# fhd-hdr.net
KiCad netlist of a schematic drawn in Altium Designer
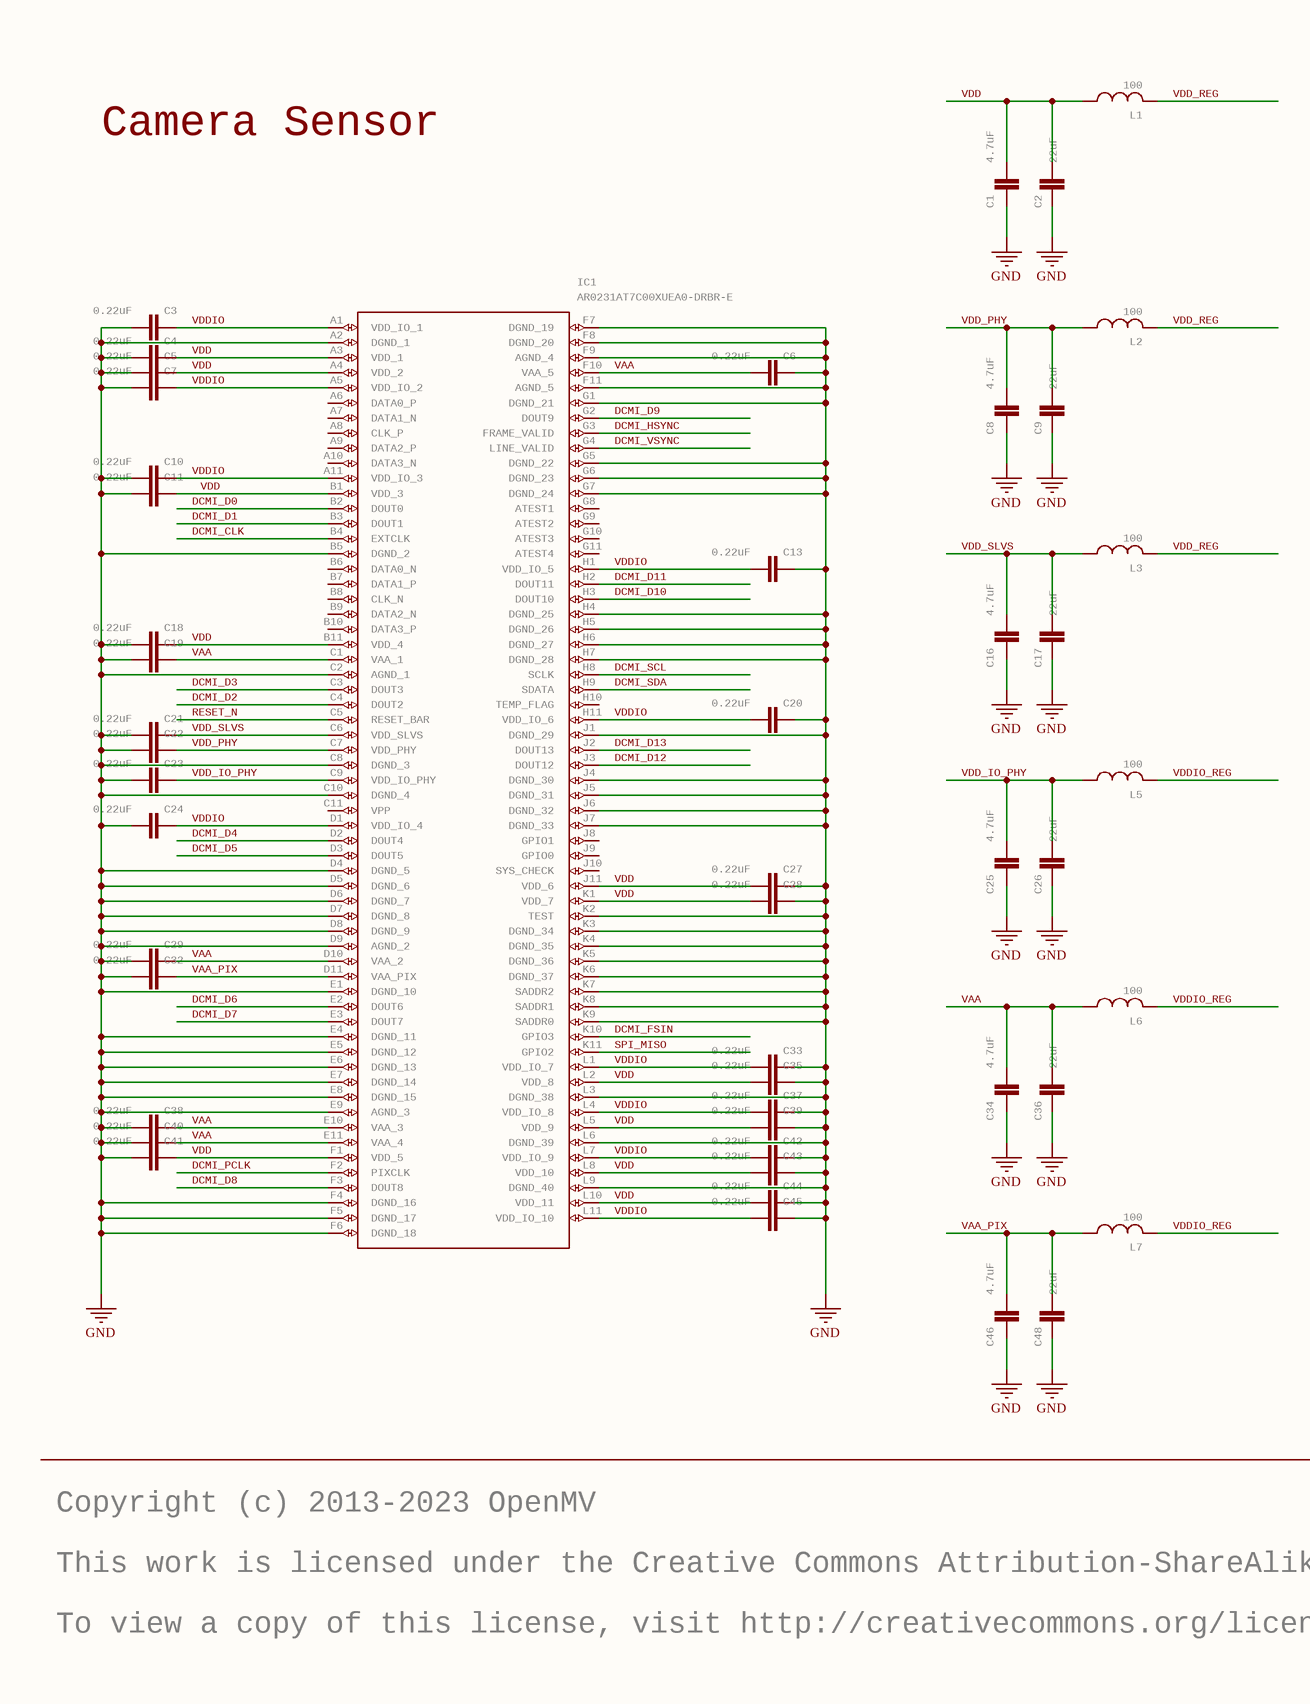
[diagram p0: fhd-hdr.SchDoc, left]
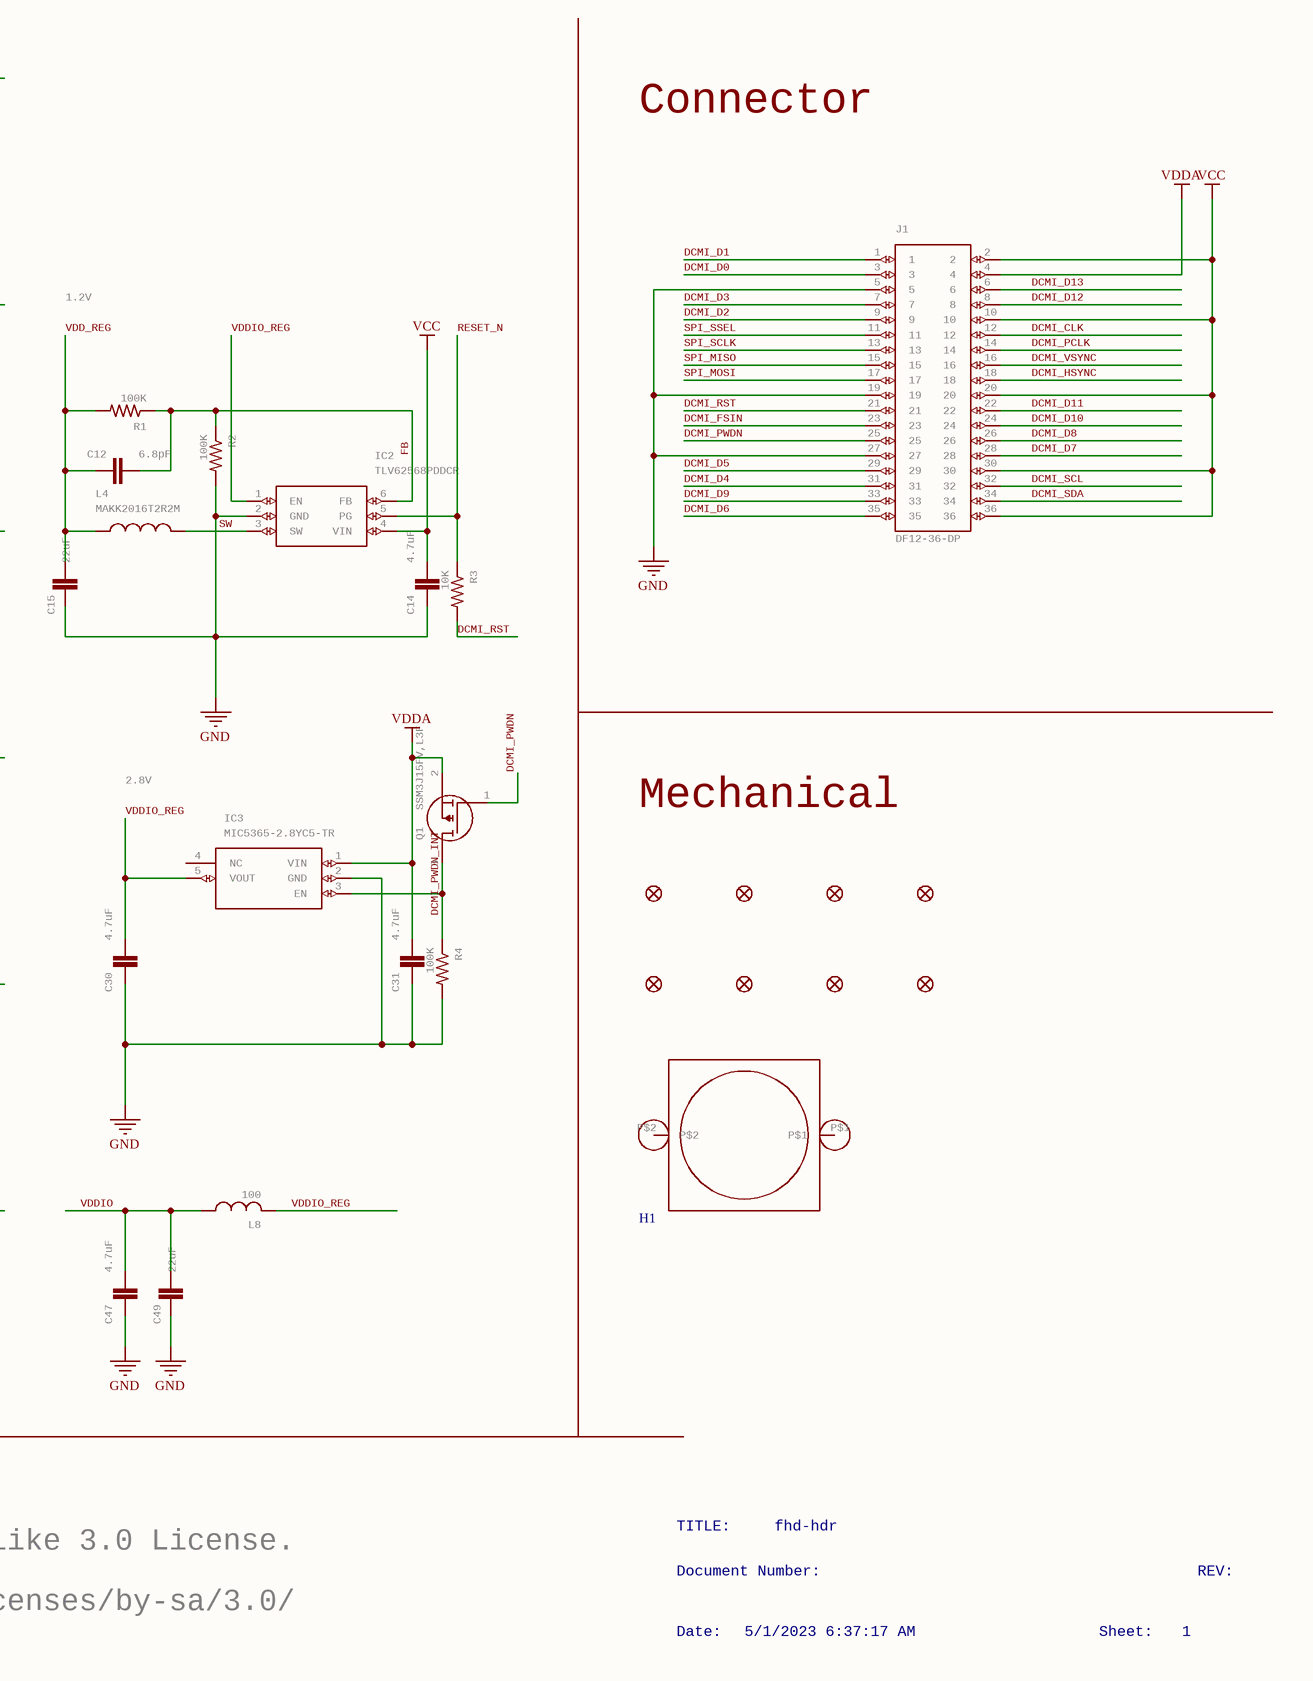
[diagram p1: fhd-hdr.SchDoc, right]

(export (version "E")
  (design (tool "Eeschema 10.0.6"))
  (components
    (comp (ref "C1")
      (value "4.7uF")
      (footprint "0402")
      (description "0402 (1005 Metric) Nick Garner - TeleSense")
      (fields (field (name "MPN") "JMK105BBJ475MV-F"))
      (libsource (lib "camera-modules") (part "CAP_0402"))
    )
    (comp (ref "C2")
      (value "22uF")
      (footprint "0805")
      (fields (field (name "MPN") "CL21A226MQQNNNE"))
      (libsource (lib "camera-modules") (part "22UF-0805-6.3V-20%"))
    )
    (comp (ref "C3")
      (value "0.22uF")
      (footprint "C0201")
      (description "CAPACITOR, European symbol")
      (fields (field (name "MPN") "GRM033R60J224ME15D"))
      (libsource (lib "camera-modules") (part "C-EUC0201"))
    )
    (comp (ref "C4")
      (value "0.22uF")
      (footprint "C0201")
      (description "CAPACITOR, European symbol")
      (fields (field (name "MPN") "GRM033R60J224ME15D"))
      (libsource (lib "camera-modules") (part "C-EUC0201"))
    )
    (comp (ref "C5")
      (value "0.22uF")
      (footprint "C0201")
      (description "CAPACITOR, European symbol")
      (fields (field (name "MPN") "GRM033R60J224ME15D"))
      (libsource (lib "camera-modules") (part "C-EUC0201"))
    )
    (comp (ref "C6")
      (value "0.22uF")
      (footprint "C0201")
      (description "CAPACITOR, European symbol")
      (fields (field (name "MPN") "GRM033R60J224ME15D"))
      (libsource (lib "camera-modules") (part "C-EUC0201"))
    )
    (comp (ref "C7")
      (value "0.22uF")
      (footprint "C0201")
      (description "CAPACITOR, European symbol")
      (fields (field (name "MPN") "GRM033R60J224ME15D"))
      (libsource (lib "camera-modules") (part "C-EUC0201"))
    )
    (comp (ref "C8")
      (value "4.7uF")
      (footprint "0402")
      (description "0402 (1005 Metric) Nick Garner - TeleSense")
      (fields (field (name "MPN") "JMK105BBJ475MV-F"))
      (libsource (lib "camera-modules") (part "CAP_0402"))
    )
    (comp (ref "C9")
      (value "22uF")
      (footprint "0805")
      (fields (field (name "MPN") "CL21A226MQQNNNE"))
      (libsource (lib "camera-modules") (part "22UF-0805-6.3V-20%"))
    )
    (comp (ref "C10")
      (value "0.22uF")
      (footprint "C0201")
      (description "CAPACITOR, European symbol")
      (fields (field (name "MPN") "GRM033R60J224ME15D"))
      (libsource (lib "camera-modules") (part "C-EUC0201"))
    )
    (comp (ref "C11")
      (value "0.22uF")
      (footprint "C0201")
      (description "CAPACITOR, European symbol")
      (fields (field (name "MPN") "GRM033R60J224ME15D"))
      (libsource (lib "camera-modules") (part "C-EUC0201"))
    )
    (comp (ref "C12")
      (value "6.8pF")
      (footprint "0402")
      (description "0402 (1005 Metric) Nick Garner - TeleSense")
      (fields (field (name "MPN") "GRM1555C1H6R8DA01D"))
      (libsource (lib "") (part "CAP_0402_1"))
    )
    (comp (ref "C13")
      (value "0.22uF")
      (footprint "C0201")
      (description "CAPACITOR, European symbol")
      (fields (field (name "MPN") "GRM033R60J224ME15D"))
      (libsource (lib "camera-modules") (part "C-EUC0201"))
    )
    (comp (ref "C14")
      (value "4.7uF")
      (footprint "0402")
      (description "0402 (1005 Metric) Nick Garner - TeleSense")
      (fields (field (name "MPN") "JMK105BBJ475MV-F"))
      (libsource (lib "camera-modules") (part "CAP_0402"))
    )
    (comp (ref "C15")
      (value "22uF")
      (footprint "0805")
      (fields (field (name "MPN") "CL21A226MQQNNNE"))
      (libsource (lib "camera-modules") (part "22UF-0805-6.3V-20%"))
    )
    (comp (ref "C16")
      (value "4.7uF")
      (footprint "0402")
      (description "0402 (1005 Metric) Nick Garner - TeleSense")
      (fields (field (name "MPN") "JMK105BBJ475MV-F"))
      (libsource (lib "camera-modules") (part "CAP_0402"))
    )
    (comp (ref "C17")
      (value "22uF")
      (footprint "0805")
      (fields (field (name "MPN") "CL21A226MQQNNNE"))
      (libsource (lib "camera-modules") (part "22UF-0805-6.3V-20%"))
    )
    (comp (ref "C18")
      (value "0.22uF")
      (footprint "C0201")
      (description "CAPACITOR, European symbol")
      (fields (field (name "MPN") "GRM033R60J224ME15D"))
      (libsource (lib "camera-modules") (part "C-EUC0201"))
    )
    (comp (ref "C19")
      (value "0.22uF")
      (footprint "C0201")
      (description "CAPACITOR, European symbol")
      (fields (field (name "MPN") "GRM033R60J224ME15D"))
      (libsource (lib "camera-modules") (part "C-EUC0201"))
    )
    (comp (ref "C20")
      (value "0.22uF")
      (footprint "C0201")
      (description "CAPACITOR, European symbol")
      (fields (field (name "MPN") "GRM033R60J224ME15D"))
      (libsource (lib "camera-modules") (part "C-EUC0201"))
    )
    (comp (ref "C21")
      (value "0.22uF")
      (footprint "C0201")
      (description "CAPACITOR, European symbol")
      (fields (field (name "MPN") "GRM033R60J224ME15D"))
      (libsource (lib "camera-modules") (part "C-EUC0201"))
    )
    (comp (ref "C22")
      (value "0.22uF")
      (footprint "C0201")
      (description "CAPACITOR, European symbol")
      (fields (field (name "MPN") "GRM033R60J224ME15D"))
      (libsource (lib "camera-modules") (part "C-EUC0201"))
    )
    (comp (ref "C23")
      (value "0.22uF")
      (footprint "C0201")
      (description "CAPACITOR, European symbol")
      (fields (field (name "MPN") "GRM033R60J224ME15D"))
      (libsource (lib "camera-modules") (part "C-EUC0201"))
    )
    (comp (ref "C24")
      (value "0.22uF")
      (footprint "C0201")
      (description "CAPACITOR, European symbol")
      (fields (field (name "MPN") "GRM033R60J224ME15D"))
      (libsource (lib "camera-modules") (part "C-EUC0201"))
    )
    (comp (ref "C25")
      (value "4.7uF")
      (footprint "0402")
      (description "0402 (1005 Metric) Nick Garner - TeleSense")
      (fields (field (name "MPN") "JMK105BBJ475MV-F"))
      (libsource (lib "camera-modules") (part "CAP_0402"))
    )
    (comp (ref "C26")
      (value "22uF")
      (footprint "0805")
      (fields (field (name "MPN") "CL21A226MQQNNNE"))
      (libsource (lib "camera-modules") (part "22UF-0805-6.3V-20%"))
    )
    (comp (ref "C27")
      (value "0.22uF")
      (footprint "C0201")
      (description "CAPACITOR, European symbol")
      (fields (field (name "MPN") "GRM033R60J224ME15D"))
      (libsource (lib "camera-modules") (part "C-EUC0201"))
    )
    (comp (ref "C28")
      (value "0.22uF")
      (footprint "C0201")
      (description "CAPACITOR, European symbol")
      (fields (field (name "MPN") "GRM033R60J224ME15D"))
      (libsource (lib "camera-modules") (part "C-EUC0201"))
    )
    (comp (ref "C29")
      (value "0.22uF")
      (footprint "C0201")
      (description "CAPACITOR, European symbol")
      (fields (field (name "MPN") "GRM033R60J224ME15D"))
      (libsource (lib "camera-modules") (part "C-EUC0201"))
    )
    (comp (ref "C30")
      (value "4.7uF")
      (footprint "0402")
      (description "0402 (1005 Metric) Nick Garner - TeleSense")
      (fields (field (name "MPN") "JMK105BBJ475MV-F"))
      (libsource (lib "camera-modules") (part "CAP_0402"))
    )
    (comp (ref "C31")
      (value "4.7uF")
      (footprint "0402")
      (description "0402 (1005 Metric) Nick Garner - TeleSense")
      (fields (field (name "MPN") "JMK105BBJ475MV-F"))
      (libsource (lib "camera-modules") (part "CAP_0402"))
    )
    (comp (ref "C32")
      (value "0.22uF")
      (footprint "C0201")
      (description "CAPACITOR, European symbol")
      (fields (field (name "MPN") "GRM033R60J224ME15D"))
      (libsource (lib "camera-modules") (part "C-EUC0201"))
    )
    (comp (ref "C33")
      (value "0.22uF")
      (footprint "C0201")
      (description "CAPACITOR, European symbol")
      (fields (field (name "MPN") "GRM033R60J224ME15D"))
      (libsource (lib "camera-modules") (part "C-EUC0201"))
    )
    (comp (ref "C34")
      (value "4.7uF")
      (footprint "0402")
      (description "0402 (1005 Metric) Nick Garner - TeleSense")
      (fields (field (name "MPN") "JMK105BBJ475MV-F"))
      (libsource (lib "camera-modules") (part "CAP_0402"))
    )
    (comp (ref "C35")
      (value "0.22uF")
      (footprint "C0201")
      (description "CAPACITOR, European symbol")
      (fields (field (name "MPN") "GRM033R60J224ME15D"))
      (libsource (lib "camera-modules") (part "C-EUC0201"))
    )
    (comp (ref "C36")
      (value "22uF")
      (footprint "0805")
      (fields (field (name "MPN") "CL21A226MQQNNNE"))
      (libsource (lib "camera-modules") (part "22UF-0805-6.3V-20%"))
    )
    (comp (ref "C37")
      (value "0.22uF")
      (footprint "C0201")
      (description "CAPACITOR, European symbol")
      (fields (field (name "MPN") "GRM033R60J224ME15D"))
      (libsource (lib "camera-modules") (part "C-EUC0201"))
    )
    (comp (ref "C38")
      (value "0.22uF")
      (footprint "C0201")
      (description "CAPACITOR, European symbol")
      (fields (field (name "MPN") "GRM033R60J224ME15D"))
      (libsource (lib "camera-modules") (part "C-EUC0201"))
    )
    (comp (ref "C39")
      (value "0.22uF")
      (footprint "C0201")
      (description "CAPACITOR, European symbol")
      (fields (field (name "MPN") "GRM033R60J224ME15D"))
      (libsource (lib "camera-modules") (part "C-EUC0201"))
    )
    (comp (ref "C40")
      (value "0.22uF")
      (footprint "C0201")
      (description "CAPACITOR, European symbol")
      (fields (field (name "MPN") "GRM033R60J224ME15D"))
      (libsource (lib "camera-modules") (part "C-EUC0201"))
    )
    (comp (ref "C41")
      (value "0.22uF")
      (footprint "C0201")
      (description "CAPACITOR, European symbol")
      (fields (field (name "MPN") "GRM033R60J224ME15D"))
      (libsource (lib "camera-modules") (part "C-EUC0201"))
    )
    (comp (ref "C42")
      (value "0.22uF")
      (footprint "C0201")
      (description "CAPACITOR, European symbol")
      (fields (field (name "MPN") "GRM033R60J224ME15D"))
      (libsource (lib "camera-modules") (part "C-EUC0201"))
    )
    (comp (ref "C43")
      (value "0.22uF")
      (footprint "C0201")
      (description "CAPACITOR, European symbol")
      (fields (field (name "MPN") "GRM033R60J224ME15D"))
      (libsource (lib "camera-modules") (part "C-EUC0201"))
    )
    (comp (ref "C44")
      (value "0.22uF")
      (footprint "C0201")
      (description "CAPACITOR, European symbol")
      (fields (field (name "MPN") "GRM033R60J224ME15D"))
      (libsource (lib "camera-modules") (part "C-EUC0201"))
    )
    (comp (ref "C45")
      (value "0.22uF")
      (footprint "C0201")
      (description "CAPACITOR, European symbol")
      (fields (field (name "MPN") "GRM033R60J224ME15D"))
      (libsource (lib "camera-modules") (part "C-EUC0201"))
    )
    (comp (ref "C46")
      (value "4.7uF")
      (footprint "0402")
      (description "0402 (1005 Metric) Nick Garner - TeleSense")
      (fields (field (name "MPN") "JMK105BBJ475MV-F"))
      (libsource (lib "camera-modules") (part "CAP_0402"))
    )
    (comp (ref "C47")
      (value "4.7uF")
      (footprint "0402")
      (description "0402 (1005 Metric) Nick Garner - TeleSense")
      (fields (field (name "MPN") "JMK105BBJ475MV-F"))
      (libsource (lib "camera-modules") (part "CAP_0402"))
    )
    (comp (ref "C48")
      (value "22uF")
      (footprint "0805")
      (fields (field (name "MPN") "CL21A226MQQNNNE"))
      (libsource (lib "camera-modules") (part "22UF-0805-6.3V-20%"))
    )
    (comp (ref "C49")
      (value "22uF")
      (footprint "0805")
      (fields (field (name "MPN") "CL21A226MQQNNNE"))
      (libsource (lib "camera-modules") (part "22UF-0805-6.3V-20%"))
    )
    (comp (ref "FD1")
      (value "FIDUCIAL1X2")
      (footprint "FIDUCIAL-1X2")
      (fields (field (name "LIBRARYNAME") "SparkFun-Aesthetics"))
      (libsource (lib "camera-modules") (part "FIDUCIAL1X2"))
    )
    (comp (ref "FD2")
      (value "FIDUCIAL1X2")
      (footprint "FIDUCIAL-1X2")
      (fields (field (name "LIBRARYNAME") "SparkFun-Aesthetics"))
      (libsource (lib "camera-modules") (part "FIDUCIAL1X2"))
    )
    (comp (ref "FD3")
      (value "FIDUCIAL1X2")
      (footprint "FIDUCIAL-1X2")
      (fields (field (name "LIBRARYNAME") "SparkFun-Aesthetics"))
      (libsource (lib "camera-modules") (part "FIDUCIAL1X2"))
    )
    (comp (ref "FD4")
      (value "FIDUCIAL1X2")
      (footprint "FIDUCIAL-1X2")
      (fields (field (name "LIBRARYNAME") "SparkFun-Aesthetics"))
      (libsource (lib "camera-modules") (part "FIDUCIAL1X2"))
    )
    (comp (ref "FD5")
      (value "FIDUCIAL1X2")
      (footprint "FIDUCIAL-1X2")
      (fields (field (name "LIBRARYNAME") "SparkFun-Aesthetics"))
      (libsource (lib "camera-modules") (part "FIDUCIAL1X2"))
    )
    (comp (ref "FD6")
      (value "FIDUCIAL1X2")
      (footprint "FIDUCIAL-1X2")
      (fields (field (name "LIBRARYNAME") "SparkFun-Aesthetics"))
      (libsource (lib "camera-modules") (part "FIDUCIAL1X2"))
    )
    (comp (ref "FD7")
      (value "FIDUCIAL1X2")
      (footprint "FIDUCIAL-1X2")
      (fields (field (name "LIBRARYNAME") "SparkFun-Aesthetics"))
      (libsource (lib "camera-modules") (part "FIDUCIAL1X2"))
    )
    (comp (ref "FD8")
      (value "FIDUCIAL1X2")
      (footprint "FIDUCIAL-1X2")
      (fields (field (name "LIBRARYNAME") "SparkFun-Aesthetics"))
      (libsource (lib "camera-modules") (part "FIDUCIAL1X2"))
    )
    (comp (ref "H1")
      (value "LENSMOUNT20MM")
      (footprint "LENSMOUNT-20MM")
      (libsource (lib "camera-modules") (part "LENSMOUNT20MM"))
    )
    (comp (ref "IC1")
      (value "AR0231AT7C00XUEA0-DRBR-E")
      (footprint "BGA121C80P11X11_1100X1000X155")
      (description "Image Sensor Color CMOS 1928 x 1208Pixels   Source:  Datasheet")
      (fields
        (field (name "ARROW_PART_NUMBER") "ARROW_PART_NUMBER")
        (field (name "MOUSER_PART_NUMBER") "MOUSER_PART_NUMBER")
      )
      (libsource (lib "camera-modules") (part "AR0231AT7C00XUEA0-DRBR-E"))
    )
    (comp (ref "IC2")
      (value "TLV62568PDDCR")
      (footprint "SOT95P280X110-6N")
      (fields (field (name "MOUSER_PART_NUMBER") "595-TLV62568PDDCR"))
      (libsource (lib "camera-modules") (part "TLV62568PDDCR"))
    )
    (comp (ref "IC3")
      (value "MIC5365-2.8YC5-TR")
      (footprint "SOT65P210X110-5N")
      (description "IC REG LINEAR 2.8V 150MA SC70-5   Source:  Datasheet")
      (fields (field (name "MOUSER_PART_NUMBER") "998-MIC5365-2.8YC5TR"))
      (libsource (lib "camera-modules") (part "MIC5365-2.8YC5-TR"))
    )
    (comp (ref "J1")
      (value "DF12-36-DP")
      (footprint "DF12-36-DP")
      (fields (field (name "MPN") "DF12NB(3.0)-36DP-0.5V(51)"))
      (libsource (lib "camera-modules") (part "DF12-36-DP"))
    )
    (comp (ref "L1")
      (value "100")
      (footprint "0402")
      (fields (field (name "MPN") "MFBM1V1005-101-R"))
      (libsource (lib "camera-modules") (part "INDUCTOR_0402"))
    )
    (comp (ref "L2")
      (value "100")
      (footprint "0402")
      (fields (field (name "MPN") "MFBM1V1005-101-R"))
      (libsource (lib "camera-modules") (part "INDUCTOR_0402"))
    )
    (comp (ref "L3")
      (value "100")
      (footprint "0402")
      (fields (field (name "MPN") "MFBM1V1005-101-R"))
      (libsource (lib "camera-modules") (part "INDUCTOR_0402"))
    )
    (comp (ref "L4")
      (value "MAKK2016T2R2M")
      (footprint "INDC2016X100N")
      (description "INDUCTOR, METAL CORE Check availability")
      (fields (field (name "MF") "Taiyo Yuden"))
      (libsource (lib "camera-modules") (part "MAKK2016T2R2M"))
    )
    (comp (ref "L5")
      (value "100")
      (footprint "0402")
      (fields (field (name "MPN") "MFBM1V1005-101-R"))
      (libsource (lib "camera-modules") (part "INDUCTOR_0402"))
    )
    (comp (ref "L6")
      (value "100")
      (footprint "0402")
      (fields (field (name "MPN") "MFBM1V1005-101-R"))
      (libsource (lib "camera-modules") (part "INDUCTOR_0402"))
    )
    (comp (ref "L7")
      (value "100")
      (footprint "0402")
      (fields (field (name "MPN") "MFBM1V1005-101-R"))
      (libsource (lib "camera-modules") (part "INDUCTOR_0402"))
    )
    (comp (ref "L8")
      (value "100")
      (footprint "0402")
      (fields (field (name "MPN") "MFBM1V1005-101-R"))
      (libsource (lib "camera-modules") (part "INDUCTOR_0402"))
    )
    (comp (ref "Q1")
      (value "SSM3J15FV,L3F")
      (footprint "SSM3J15FV")
      (description "MOSFET 30 V, P-channel Trench MOSFET   Source:  Datasheet")
      (libsource (lib "camera-modules") (part "PMXB120EPEZ"))
    )
    (comp (ref "R1")
      (value "100K")
      (footprint "R0402")
      (description "RESISTOR, American symbol")
      (fields (field (name "MPN") "AC0402FR-07100KL"))
      (libsource (lib "camera-modules") (part "R-US_R0402"))
    )
    (comp (ref "R2")
      (value "100K")
      (footprint "R0402")
      (description "RESISTOR, American symbol")
      (fields (field (name "MPN") "AC0402FR-07100KL"))
      (libsource (lib "camera-modules") (part "R-US_R0402"))
    )
    (comp (ref "R3")
      (value "10K")
      (footprint "R0402")
      (description "RESISTOR, American symbol")
      (fields (field (name "MPN") "AC0402FR-1310KL"))
      (libsource (lib "camera-modules") (part "R-US_R0402"))
    )
    (comp (ref "R4")
      (value "100K")
      (footprint "R0402")
      (description "RESISTOR, American symbol")
      (fields (field (name "MPN") "AC0402FR-07100KL"))
      (libsource (lib "camera-modules") (part "R-US_R0402"))
    )
  )
  (nets
    (net (code "1") (name "/DCMI_CLK") (class "Default")
      (node (ref "IC1") (pin "B4") (pinfunction "EXTCLK_B4") (pintype "bidirectional"))
      (node (ref "J1") (pin "12") (pinfunction "12_12") (pintype "bidirectional"))
    )
    (net (code "2") (name "/DCMI_D0") (class "Default")
      (node (ref "IC1") (pin "B2") (pinfunction "DOUT0_B2") (pintype "bidirectional"))
      (node (ref "J1") (pin "3") (pinfunction "3_3") (pintype "bidirectional"))
    )
    (net (code "3") (name "/DCMI_D1") (class "Default")
      (node (ref "IC1") (pin "B3") (pinfunction "DOUT1_B3") (pintype "bidirectional"))
      (node (ref "J1") (pin "1") (pinfunction "1_1") (pintype "bidirectional"))
    )
    (net (code "4") (name "/DCMI_D2") (class "Default")
      (node (ref "IC1") (pin "C4") (pinfunction "DOUT2_C4") (pintype "bidirectional"))
      (node (ref "J1") (pin "9") (pinfunction "9_9") (pintype "bidirectional"))
    )
    (net (code "5") (name "/DCMI_D3") (class "Default")
      (node (ref "IC1") (pin "C3") (pinfunction "DOUT3_C3") (pintype "bidirectional"))
      (node (ref "J1") (pin "7") (pinfunction "7_7") (pintype "bidirectional"))
    )
    (net (code "6") (name "/DCMI_D4") (class "Default")
      (node (ref "IC1") (pin "D2") (pinfunction "DOUT4_D2") (pintype "bidirectional"))
      (node (ref "J1") (pin "31") (pinfunction "31_31") (pintype "bidirectional"))
    )
    (net (code "7") (name "/DCMI_D5") (class "Default")
      (node (ref "IC1") (pin "D3") (pinfunction "DOUT5_D3") (pintype "bidirectional"))
      (node (ref "J1") (pin "29") (pinfunction "29_29") (pintype "bidirectional"))
    )
    (net (code "8") (name "/DCMI_D6") (class "Default")
      (node (ref "IC1") (pin "E2") (pinfunction "DOUT6_E2") (pintype "bidirectional"))
      (node (ref "J1") (pin "35") (pinfunction "35_35") (pintype "bidirectional"))
    )
    (net (code "9") (name "/DCMI_D7") (class "Default")
      (node (ref "IC1") (pin "E3") (pinfunction "DOUT7_E3") (pintype "bidirectional"))
      (node (ref "J1") (pin "28") (pinfunction "28_28") (pintype "bidirectional"))
    )
    (net (code "10") (name "/DCMI_D8") (class "Default")
      (node (ref "IC1") (pin "F3") (pinfunction "DOUT8_F3") (pintype "bidirectional"))
      (node (ref "J1") (pin "26") (pinfunction "26_26") (pintype "bidirectional"))
    )
    (net (code "11") (name "/DCMI_D9") (class "Default")
      (node (ref "IC1") (pin "G2") (pinfunction "DOUT9_G2") (pintype "bidirectional"))
      (node (ref "J1") (pin "33") (pinfunction "33_33") (pintype "bidirectional"))
    )
    (net (code "12") (name "/DCMI_D10") (class "Default")
      (node (ref "IC1") (pin "H3") (pinfunction "DOUT10_H3") (pintype "bidirectional"))
      (node (ref "J1") (pin "24") (pinfunction "24_24") (pintype "bidirectional"))
    )
    (net (code "13") (name "/DCMI_D11") (class "Default")
      (node (ref "IC1") (pin "H2") (pinfunction "DOUT11_H2") (pintype "bidirectional"))
      (node (ref "J1") (pin "22") (pinfunction "22_22") (pintype "bidirectional"))
    )
    (net (code "14") (name "/DCMI_D12") (class "Default")
      (node (ref "IC1") (pin "J3") (pinfunction "DOUT12_J3") (pintype "bidirectional"))
      (node (ref "J1") (pin "8") (pinfunction "8_8") (pintype "bidirectional"))
    )
    (net (code "15") (name "/DCMI_D13") (class "Default")
      (node (ref "IC1") (pin "J2") (pinfunction "DOUT13_J2") (pintype "bidirectional"))
      (node (ref "J1") (pin "6") (pinfunction "6_6") (pintype "bidirectional"))
    )
    (net (code "16") (name "/DCMI_FSIN") (class "Default")
      (node (ref "IC1") (pin "K10") (pinfunction "GPIO3_K10") (pintype "bidirectional"))
      (node (ref "J1") (pin "23") (pinfunction "23_23") (pintype "bidirectional"))
    )
    (net (code "17") (name "/DCMI_HSYNC") (class "Default")
      (node (ref "IC1") (pin "G3") (pinfunction "FRAME_VALID_G3") (pintype "bidirectional"))
      (node (ref "J1") (pin "18") (pinfunction "18_18") (pintype "bidirectional"))
    )
    (net (code "18") (name "/DCMI_PCLK") (class "Default")
      (node (ref "IC1") (pin "F2") (pinfunction "PIXCLK_F2") (pintype "bidirectional"))
      (node (ref "J1") (pin "14") (pinfunction "14_14") (pintype "bidirectional"))
    )
    (net (code "19") (name "/DCMI_PWDN") (class "Default")
      (node (ref "J1") (pin "25") (pinfunction "25_25") (pintype "bidirectional"))
      (node (ref "Q1") (pin "1") (pinfunction "G_1") (pintype "bidirectional"))
    )
    (net (code "20") (name "/DCMI_PWDN_INT") (class "Default")
      (node (ref "IC3") (pin "3") (pinfunction "EN_3") (pintype "bidirectional"))
      (node (ref "Q1") (pin "3") (pinfunction "D_3") (pintype "bidirectional"))
      (node (ref "R4") (pin "1") (pinfunction "1_1") (pintype "passive"))
    )
    (net (code "21") (name "/DCMI_RST") (class "Default")
      (node (ref "J1") (pin "21") (pinfunction "21_21") (pintype "bidirectional"))
      (node (ref "R3") (pin "2") (pinfunction "2_2") (pintype "passive"))
    )
    (net (code "22") (name "/DCMI_SCL") (class "Default")
      (node (ref "IC1") (pin "H8") (pinfunction "SCLK_H8") (pintype "bidirectional"))
      (node (ref "J1") (pin "32") (pinfunction "32_32") (pintype "bidirectional"))
    )
    (net (code "23") (name "/DCMI_SDA") (class "Default")
      (node (ref "IC1") (pin "H9") (pinfunction "SDATA_H9") (pintype "bidirectional"))
      (node (ref "J1") (pin "34") (pinfunction "34_34") (pintype "bidirectional"))
    )
    (net (code "24") (name "/DCMI_VSYNC") (class "Default")
      (node (ref "IC1") (pin "G4") (pinfunction "LINE_VALID_G4") (pintype "bidirectional"))
      (node (ref "J1") (pin "16") (pinfunction "16_16") (pintype "bidirectional"))
    )
    (net (code "25") (name "/FB") (class "Default")
      (node (ref "C12") (pin "2") (pinfunction "2_2") (pintype "passive"))
      (node (ref "IC2") (pin "6") (pinfunction "FB_6") (pintype "bidirectional"))
      (node (ref "R1") (pin "1") (pinfunction "1_1") (pintype "passive"))
      (node (ref "R2") (pin "1") (pinfunction "1_1") (pintype "passive"))
    )
    (net (code "26") (name "/RESET_N") (class "Default")
      (node (ref "IC1") (pin "C5") (pinfunction "RESET_BAR_C5") (pintype "bidirectional"))
      (node (ref "IC2") (pin "5") (pinfunction "PG_5") (pintype "bidirectional"))
      (node (ref "R3") (pin "1") (pinfunction "1_1") (pintype "passive"))
    )
    (net (code "27") (name "/SPI_MISO") (class "Default")
      (node (ref "IC1") (pin "K11") (pinfunction "GPIO2_K11") (pintype "bidirectional"))
      (node (ref "J1") (pin "15") (pinfunction "15_15") (pintype "bidirectional"))
    )
    (net (code "28") (name "/SPI_MOSI") (class "Default")
      (node (ref "J1") (pin "17") (pinfunction "17_17") (pintype "bidirectional"))
    )
    (net (code "29") (name "/SPI_SCLK") (class "Default")
      (node (ref "J1") (pin "13") (pinfunction "13_13") (pintype "bidirectional"))
    )
    (net (code "30") (name "/SPI_SSEL") (class "Default")
      (node (ref "J1") (pin "11") (pinfunction "11_11") (pintype "bidirectional"))
    )
    (net (code "31") (name "/SW") (class "Default")
      (node (ref "IC2") (pin "3") (pinfunction "SW_3") (pintype "bidirectional"))
      (node (ref "L4") (pin "2") (pinfunction "2_2") (pintype "passive"))
    )
    (net (code "32") (name "/VAA") (class "Default")
      (node (ref "C19") (pin "1") (pinfunction "1_1") (pintype "passive"))
      (node (ref "C29") (pin "1") (pinfunction "1_1") (pintype "passive"))
      (node (ref "C34") (pin "2") (pinfunction "2_2") (pintype "passive"))
      (node (ref "C36") (pin "2") (pinfunction "2_2") (pintype "passive"))
      (node (ref "C38") (pin "1") (pinfunction "1_1") (pintype "passive"))
      (node (ref "C40") (pin "1") (pinfunction "1_1") (pintype "passive"))
      (node (ref "C6") (pin "2") (pinfunction "2_2") (pintype "passive"))
      (node (ref "IC1") (pin "C1") (pinfunction "VAA_1_C1") (pintype "bidirectional"))
      (node (ref "IC1") (pin "D10") (pinfunction "VAA_2_D10") (pintype "bidirectional"))
      (node (ref "IC1") (pin "E10") (pinfunction "VAA_3_E10") (pintype "bidirectional"))
      (node (ref "IC1") (pin "E11") (pinfunction "VAA_4_E11") (pintype "bidirectional"))
      (node (ref "IC1") (pin "F10") (pinfunction "VAA_5_F10") (pintype "bidirectional"))
      (node (ref "L6") (pin "1") (pinfunction "P$1_1") (pintype "passive"))
    )
    (net (code "33") (name "/VAA_PIX") (class "Default")
      (node (ref "C32") (pin "1") (pinfunction "1_1") (pintype "passive"))
      (node (ref "C46") (pin "2") (pinfunction "2_2") (pintype "passive"))
      (node (ref "C48") (pin "2") (pinfunction "2_2") (pintype "passive"))
      (node (ref "IC1") (pin "D11") (pinfunction "VAA_PIX_D11") (pintype "bidirectional"))
      (node (ref "L7") (pin "1") (pinfunction "P$1_1") (pintype "passive"))
    )
    (net (code "34") (name "/VDD") (class "Default")
      (node (ref "C1") (pin "2") (pinfunction "2_2") (pintype "passive"))
      (node (ref "C11") (pin "1") (pinfunction "1_1") (pintype "passive"))
      (node (ref "C18") (pin "1") (pinfunction "1_1") (pintype "passive"))
      (node (ref "C2") (pin "2") (pinfunction "2_2") (pintype "passive"))
      (node (ref "C27") (pin "2") (pinfunction "2_2") (pintype "passive"))
      (node (ref "C28") (pin "2") (pinfunction "2_2") (pintype "passive"))
      (node (ref "C35") (pin "2") (pinfunction "2_2") (pintype "passive"))
      (node (ref "C39") (pin "2") (pinfunction "2_2") (pintype "passive"))
      (node (ref "C4") (pin "1") (pinfunction "1_1") (pintype "passive"))
      (node (ref "C41") (pin "1") (pinfunction "1_1") (pintype "passive"))
      (node (ref "C43") (pin "2") (pinfunction "2_2") (pintype "passive"))
      (node (ref "C44") (pin "2") (pinfunction "2_2") (pintype "passive"))
      (node (ref "C5") (pin "1") (pinfunction "1_1") (pintype "passive"))
      (node (ref "IC1") (pin "A3") (pinfunction "VDD_1_A3") (pintype "bidirectional"))
      (node (ref "IC1") (pin "A4") (pinfunction "VDD_2_A4") (pintype "bidirectional"))
      (node (ref "IC1") (pin "B1") (pinfunction "VDD_3_B1") (pintype "bidirectional"))
      (node (ref "IC1") (pin "B11") (pinfunction "VDD_4_B11") (pintype "bidirectional"))
      (node (ref "IC1") (pin "F1") (pinfunction "VDD_5_F1") (pintype "bidirectional"))
      (node (ref "IC1") (pin "J11") (pinfunction "VDD_6_J11") (pintype "bidirectional"))
      (node (ref "IC1") (pin "K1") (pinfunction "VDD_7_K1") (pintype "bidirectional"))
      (node (ref "IC1") (pin "L10") (pinfunction "VDD_11_L10") (pintype "bidirectional"))
      (node (ref "IC1") (pin "L2") (pinfunction "VDD_8_L2") (pintype "bidirectional"))
      (node (ref "IC1") (pin "L5") (pinfunction "VDD_9_L5") (pintype "bidirectional"))
      (node (ref "IC1") (pin "L8") (pinfunction "VDD_10_L8") (pintype "bidirectional"))
      (node (ref "L1") (pin "1") (pinfunction "P$1_1") (pintype "passive"))
    )
    (net (code "35") (name "/VDDIO") (class "Default")
      (node (ref "C10") (pin "1") (pinfunction "1_1") (pintype "passive"))
      (node (ref "C13") (pin "2") (pinfunction "2_2") (pintype "passive"))
      (node (ref "C20") (pin "2") (pinfunction "2_2") (pintype "passive"))
      (node (ref "C24") (pin "1") (pinfunction "1_1") (pintype "passive"))
      (node (ref "C3") (pin "1") (pinfunction "1_1") (pintype "passive"))
      (node (ref "C33") (pin "2") (pinfunction "2_2") (pintype "passive"))
      (node (ref "C37") (pin "2") (pinfunction "2_2") (pintype "passive"))
      (node (ref "C42") (pin "2") (pinfunction "2_2") (pintype "passive"))
      (node (ref "C45") (pin "2") (pinfunction "2_2") (pintype "passive"))
      (node (ref "C47") (pin "2") (pinfunction "2_2") (pintype "passive"))
      (node (ref "C49") (pin "2") (pinfunction "2_2") (pintype "passive"))
      (node (ref "C7") (pin "1") (pinfunction "1_1") (pintype "passive"))
      (node (ref "IC1") (pin "A1") (pinfunction "VDD_IO_1_A1") (pintype "bidirectional"))
      (node (ref "IC1") (pin "A11") (pinfunction "VDD_IO_3_A11") (pintype "bidirectional"))
      (node (ref "IC1") (pin "A5") (pinfunction "VDD_IO_2_A5") (pintype "bidirectional"))
      (node (ref "IC1") (pin "D1") (pinfunction "VDD_IO_4_D1") (pintype "bidirectional"))
      (node (ref "IC1") (pin "H1") (pinfunction "VDD_IO_5_H1") (pintype "bidirectional"))
      (node (ref "IC1") (pin "H11") (pinfunction "VDD_IO_6_H11") (pintype "bidirectional"))
      (node (ref "IC1") (pin "L1") (pinfunction "VDD_IO_7_L1") (pintype "bidirectional"))
      (node (ref "IC1") (pin "L11") (pinfunction "VDD_IO_10_L11") (pintype "bidirectional"))
      (node (ref "IC1") (pin "L4") (pinfunction "VDD_IO_8_L4") (pintype "bidirectional"))
      (node (ref "IC1") (pin "L7") (pinfunction "VDD_IO_9_L7") (pintype "bidirectional"))
      (node (ref "L8") (pin "1") (pinfunction "P$1_1") (pintype "passive"))
    )
    (net (code "36") (name "/VDDIO_REG") (class "Default")
      (node (ref "C30") (pin "2") (pinfunction "2_2") (pintype "passive"))
      (node (ref "IC2") (pin "1") (pinfunction "EN_1") (pintype "bidirectional"))
      (node (ref "IC3") (pin "5") (pinfunction "VOUT_5") (pintype "bidirectional"))
      (node (ref "L5") (pin "2") (pinfunction "P$2_2") (pintype "passive"))
      (node (ref "L6") (pin "2") (pinfunction "P$2_2") (pintype "passive"))
      (node (ref "L7") (pin "2") (pinfunction "P$2_2") (pintype "passive"))
      (node (ref "L8") (pin "2") (pinfunction "P$2_2") (pintype "passive"))
    )
    (net (code "37") (name "/VDD_IO_PHY") (class "Default")
      (node (ref "C23") (pin "1") (pinfunction "1_1") (pintype "passive"))
      (node (ref "C25") (pin "2") (pinfunction "2_2") (pintype "passive"))
      (node (ref "C26") (pin "2") (pinfunction "2_2") (pintype "passive"))
      (node (ref "IC1") (pin "C9") (pinfunction "VDD_IO_PHY_C9") (pintype "bidirectional"))
      (node (ref "L5") (pin "1") (pinfunction "P$1_1") (pintype "passive"))
    )
    (net (code "38") (name "/VDD_PHY") (class "Default")
      (node (ref "C22") (pin "1") (pinfunction "1_1") (pintype "passive"))
      (node (ref "C8") (pin "2") (pinfunction "2_2") (pintype "passive"))
      (node (ref "C9") (pin "2") (pinfunction "2_2") (pintype "passive"))
      (node (ref "IC1") (pin "C7") (pinfunction "VDD_PHY_C7") (pintype "bidirectional"))
      (node (ref "L2") (pin "1") (pinfunction "P$1_1") (pintype "passive"))
    )
    (net (code "39") (name "/VDD_REG") (class "Default")
      (node (ref "C12") (pin "1") (pinfunction "1_1") (pintype "passive"))
      (node (ref "C15") (pin "2") (pinfunction "2_2") (pintype "passive"))
      (node (ref "L1") (pin "2") (pinfunction "P$2_2") (pintype "passive"))
      (node (ref "L2") (pin "2") (pinfunction "P$2_2") (pintype "passive"))
      (node (ref "L3") (pin "2") (pinfunction "P$2_2") (pintype "passive"))
      (node (ref "L4") (pin "1") (pinfunction "1_1") (pintype "passive"))
      (node (ref "R1") (pin "2") (pinfunction "2_2") (pintype "passive"))
    )
    (net (code "40") (name "/VDD_SLVS") (class "Default")
      (node (ref "C16") (pin "2") (pinfunction "2_2") (pintype "passive"))
      (node (ref "C17") (pin "2") (pinfunction "2_2") (pintype "passive"))
      (node (ref "C21") (pin "1") (pinfunction "1_1") (pintype "passive"))
      (node (ref "IC1") (pin "C6") (pinfunction "VDD_SLVS_C6") (pintype "bidirectional"))
      (node (ref "L3") (pin "1") (pinfunction "P$1_1") (pintype "passive"))
    )
    (net (code "41") (name "GND") (class "Default")
      (node (ref "C1") (pin "1") (pinfunction "1_1") (pintype "passive"))
      (node (ref "C10") (pin "2") (pinfunction "2_2") (pintype "passive"))
      (node (ref "C11") (pin "2") (pinfunction "2_2") (pintype "passive"))
      (node (ref "C13") (pin "1") (pinfunction "1_1") (pintype "passive"))
      (node (ref "C14") (pin "1") (pinfunction "1_1") (pintype "passive"))
      (node (ref "C15") (pin "1") (pinfunction "1_1") (pintype "passive"))
      (node (ref "C16") (pin "1") (pinfunction "1_1") (pintype "passive"))
      (node (ref "C17") (pin "1") (pinfunction "1_1") (pintype "passive"))
      (node (ref "C18") (pin "2") (pinfunction "2_2") (pintype "passive"))
      (node (ref "C19") (pin "2") (pinfunction "2_2") (pintype "passive"))
      (node (ref "C2") (pin "1") (pinfunction "1_1") (pintype "passive"))
      (node (ref "C20") (pin "1") (pinfunction "1_1") (pintype "passive"))
      (node (ref "C21") (pin "2") (pinfunction "2_2") (pintype "passive"))
      (node (ref "C22") (pin "2") (pinfunction "2_2") (pintype "passive"))
      (node (ref "C23") (pin "2") (pinfunction "2_2") (pintype "passive"))
      (node (ref "C24") (pin "2") (pinfunction "2_2") (pintype "passive"))
      (node (ref "C25") (pin "1") (pinfunction "1_1") (pintype "passive"))
      (node (ref "C26") (pin "1") (pinfunction "1_1") (pintype "passive"))
      (node (ref "C27") (pin "1") (pinfunction "1_1") (pintype "passive"))
      (node (ref "C28") (pin "1") (pinfunction "1_1") (pintype "passive"))
      (node (ref "C29") (pin "2") (pinfunction "2_2") (pintype "passive"))
      (node (ref "C3") (pin "2") (pinfunction "2_2") (pintype "passive"))
      (node (ref "C30") (pin "1") (pinfunction "1_1") (pintype "passive"))
      (node (ref "C31") (pin "1") (pinfunction "1_1") (pintype "passive"))
      (node (ref "C32") (pin "2") (pinfunction "2_2") (pintype "passive"))
      (node (ref "C33") (pin "1") (pinfunction "1_1") (pintype "passive"))
      (node (ref "C34") (pin "1") (pinfunction "1_1") (pintype "passive"))
      (node (ref "C35") (pin "1") (pinfunction "1_1") (pintype "passive"))
      (node (ref "C36") (pin "1") (pinfunction "1_1") (pintype "passive"))
      (node (ref "C37") (pin "1") (pinfunction "1_1") (pintype "passive"))
      (node (ref "C38") (pin "2") (pinfunction "2_2") (pintype "passive"))
      (node (ref "C39") (pin "1") (pinfunction "1_1") (pintype "passive"))
      (node (ref "C4") (pin "2") (pinfunction "2_2") (pintype "passive"))
      (node (ref "C40") (pin "2") (pinfunction "2_2") (pintype "passive"))
      (node (ref "C41") (pin "2") (pinfunction "2_2") (pintype "passive"))
      (node (ref "C42") (pin "1") (pinfunction "1_1") (pintype "passive"))
      (node (ref "C43") (pin "1") (pinfunction "1_1") (pintype "passive"))
      (node (ref "C44") (pin "1") (pinfunction "1_1") (pintype "passive"))
      (node (ref "C45") (pin "1") (pinfunction "1_1") (pintype "passive"))
      (node (ref "C46") (pin "1") (pinfunction "1_1") (pintype "passive"))
      (node (ref "C47") (pin "1") (pinfunction "1_1") (pintype "passive"))
      (node (ref "C48") (pin "1") (pinfunction "1_1") (pintype "passive"))
      (node (ref "C49") (pin "1") (pinfunction "1_1") (pintype "passive"))
      (node (ref "C5") (pin "2") (pinfunction "2_2") (pintype "passive"))
      (node (ref "C6") (pin "1") (pinfunction "1_1") (pintype "passive"))
      (node (ref "C7") (pin "2") (pinfunction "2_2") (pintype "passive"))
      (node (ref "C8") (pin "1") (pinfunction "1_1") (pintype "passive"))
      (node (ref "C9") (pin "1") (pinfunction "1_1") (pintype "passive"))
      (node (ref "IC1") (pin "A2") (pinfunction "DGND_1_A2") (pintype "bidirectional"))
      (node (ref "IC1") (pin "B5") (pinfunction "DGND_2_B5") (pintype "bidirectional"))
      (node (ref "IC1") (pin "C10") (pinfunction "DGND_4_C10") (pintype "bidirectional"))
      (node (ref "IC1") (pin "C2") (pinfunction "AGND_1_C2") (pintype "bidirectional"))
      (node (ref "IC1") (pin "C8") (pinfunction "DGND_3_C8") (pintype "bidirectional"))
      (node (ref "IC1") (pin "D4") (pinfunction "DGND_5_D4") (pintype "bidirectional"))
      (node (ref "IC1") (pin "D5") (pinfunction "DGND_6_D5") (pintype "bidirectional"))
      (node (ref "IC1") (pin "D6") (pinfunction "DGND_7_D6") (pintype "bidirectional"))
      (node (ref "IC1") (pin "D7") (pinfunction "DGND_8_D7") (pintype "bidirectional"))
      (node (ref "IC1") (pin "D8") (pinfunction "DGND_9_D8") (pintype "bidirectional"))
      (node (ref "IC1") (pin "D9") (pinfunction "AGND_2_D9") (pintype "bidirectional"))
      (node (ref "IC1") (pin "E1") (pinfunction "DGND_10_E1") (pintype "bidirectional"))
      (node (ref "IC1") (pin "E4") (pinfunction "DGND_11_E4") (pintype "bidirectional"))
      (node (ref "IC1") (pin "E5") (pinfunction "DGND_12_E5") (pintype "bidirectional"))
      (node (ref "IC1") (pin "E6") (pinfunction "DGND_13_E6") (pintype "bidirectional"))
      (node (ref "IC1") (pin "E7") (pinfunction "DGND_14_E7") (pintype "bidirectional"))
      (node (ref "IC1") (pin "E8") (pinfunction "DGND_15_E8") (pintype "bidirectional"))
      (node (ref "IC1") (pin "E9") (pinfunction "AGND_3_E9") (pintype "bidirectional"))
      (node (ref "IC1") (pin "F11") (pinfunction "AGND_5_F11") (pintype "bidirectional"))
      (node (ref "IC1") (pin "F4") (pinfunction "DGND_16_F4") (pintype "bidirectional"))
      (node (ref "IC1") (pin "F5") (pinfunction "DGND_17_F5") (pintype "bidirectional"))
      (node (ref "IC1") (pin "F6") (pinfunction "DGND_18_F6") (pintype "bidirectional"))
      (node (ref "IC1") (pin "F7") (pinfunction "DGND_19_F7") (pintype "bidirectional"))
      (node (ref "IC1") (pin "F8") (pinfunction "DGND_20_F8") (pintype "bidirectional"))
      (node (ref "IC1") (pin "F9") (pinfunction "AGND_4_F9") (pintype "bidirectional"))
      (node (ref "IC1") (pin "G1") (pinfunction "DGND_21_G1") (pintype "bidirectional"))
      (node (ref "IC1") (pin "G5") (pinfunction "DGND_22_G5") (pintype "bidirectional"))
      (node (ref "IC1") (pin "G6") (pinfunction "DGND_23_G6") (pintype "bidirectional"))
      (node (ref "IC1") (pin "G7") (pinfunction "DGND_24_G7") (pintype "bidirectional"))
      (node (ref "IC1") (pin "H4") (pinfunction "DGND_25_H4") (pintype "bidirectional"))
      (node (ref "IC1") (pin "H5") (pinfunction "DGND_26_H5") (pintype "bidirectional"))
      (node (ref "IC1") (pin "H6") (pinfunction "DGND_27_H6") (pintype "bidirectional"))
      (node (ref "IC1") (pin "H7") (pinfunction "DGND_28_H7") (pintype "bidirectional"))
      (node (ref "IC1") (pin "J1") (pinfunction "DGND_29_J1") (pintype "bidirectional"))
      (node (ref "IC1") (pin "J4") (pinfunction "DGND_30_J4") (pintype "bidirectional"))
      (node (ref "IC1") (pin "J5") (pinfunction "DGND_31_J5") (pintype "bidirectional"))
      (node (ref "IC1") (pin "J6") (pinfunction "DGND_32_J6") (pintype "bidirectional"))
      (node (ref "IC1") (pin "J7") (pinfunction "DGND_33_J7") (pintype "bidirectional"))
      (node (ref "IC1") (pin "K2") (pinfunction "TEST_K2") (pintype "bidirectional"))
      (node (ref "IC1") (pin "K3") (pinfunction "DGND_34_K3") (pintype "bidirectional"))
      (node (ref "IC1") (pin "K4") (pinfunction "DGND_35_K4") (pintype "bidirectional"))
      (node (ref "IC1") (pin "K5") (pinfunction "DGND_36_K5") (pintype "bidirectional"))
      (node (ref "IC1") (pin "K6") (pinfunction "DGND_37_K6") (pintype "bidirectional"))
      (node (ref "IC1") (pin "K7") (pinfunction "SADDR2_K7") (pintype "bidirectional"))
      (node (ref "IC1") (pin "K8") (pinfunction "SADDR1_K8") (pintype "bidirectional"))
      (node (ref "IC1") (pin "K9") (pinfunction "SADDR0_K9") (pintype "bidirectional"))
      (node (ref "IC1") (pin "L3") (pinfunction "DGND_38_L3") (pintype "bidirectional"))
      (node (ref "IC1") (pin "L6") (pinfunction "DGND_39_L6") (pintype "bidirectional"))
      (node (ref "IC1") (pin "L9") (pinfunction "DGND_40_L9") (pintype "bidirectional"))
      (node (ref "IC2") (pin "2") (pinfunction "GND_2") (pintype "bidirectional"))
      (node (ref "IC3") (pin "2") (pinfunction "GND_2") (pintype "bidirectional"))
      (node (ref "J1") (pin "19") (pinfunction "19_19") (pintype "bidirectional"))
      (node (ref "J1") (pin "27") (pinfunction "27_27") (pintype "bidirectional"))
      (node (ref "J1") (pin "5") (pinfunction "5_5") (pintype "bidirectional"))
      (node (ref "R2") (pin "2") (pinfunction "2_2") (pintype "passive"))
      (node (ref "R4") (pin "2") (pinfunction "2_2") (pintype "passive"))
    )
    (net (code "42") (name "VCC") (class "Default")
      (node (ref "C14") (pin "2") (pinfunction "2_2") (pintype "passive"))
      (node (ref "IC2") (pin "4") (pinfunction "VIN_4") (pintype "bidirectional"))
      (node (ref "J1") (pin "10") (pinfunction "10_10") (pintype "bidirectional"))
      (node (ref "J1") (pin "2") (pinfunction "2_2") (pintype "bidirectional"))
      (node (ref "J1") (pin "20") (pinfunction "20_20") (pintype "bidirectional"))
      (node (ref "J1") (pin "30") (pinfunction "30_30") (pintype "bidirectional"))
      (node (ref "J1") (pin "36") (pinfunction "36_36") (pintype "bidirectional"))
    )
    (net (code "43") (name "VDDA") (class "Default")
      (node (ref "C31") (pin "2") (pinfunction "2_2") (pintype "passive"))
      (node (ref "IC3") (pin "1") (pinfunction "VIN_1") (pintype "bidirectional"))
      (node (ref "J1") (pin "4") (pinfunction "4_4") (pintype "bidirectional"))
      (node (ref "Q1") (pin "2") (pinfunction "S_2") (pintype "bidirectional"))
    )
    (net (code "44") (name "unconnected-(H1-PadP$1)") (class "Default")
      (node (ref "H1") (pin "P$1") (pinfunction "P$1_P$1") (pintype "power_in"))
    )
    (net (code "45") (name "unconnected-(H1-PadP$2)") (class "Default")
      (node (ref "H1") (pin "P$2") (pinfunction "P$2_P$2") (pintype "power_in"))
    )
    (net (code "46") (name "unconnected-(IC1-ATEST1-PadG8)") (class "Default")
      (node (ref "IC1") (pin "G8") (pinfunction "ATEST1_G8") (pintype "bidirectional"))
    )
    (net (code "47") (name "unconnected-(IC1-ATEST2-PadG9)") (class "Default")
      (node (ref "IC1") (pin "G9") (pinfunction "ATEST2_G9") (pintype "bidirectional"))
    )
    (net (code "48") (name "unconnected-(IC1-ATEST3-PadG10)") (class "Default")
      (node (ref "IC1") (pin "G10") (pinfunction "ATEST3_G10") (pintype "bidirectional"))
    )
    (net (code "49") (name "unconnected-(IC1-ATEST4-PadG11)") (class "Default")
      (node (ref "IC1") (pin "G11") (pinfunction "ATEST4_G11") (pintype "bidirectional"))
    )
    (net (code "50") (name "unconnected-(IC1-CLK_N-PadB8)") (class "Default")
      (node (ref "IC1") (pin "B8") (pinfunction "CLK_N_B8") (pintype "bidirectional"))
    )
    (net (code "51") (name "unconnected-(IC1-CLK_P-PadA8)") (class "Default")
      (node (ref "IC1") (pin "A8") (pinfunction "CLK_P_A8") (pintype "bidirectional"))
    )
    (net (code "52") (name "unconnected-(IC1-DATA0_N-PadB6)") (class "Default")
      (node (ref "IC1") (pin "B6") (pinfunction "DATA0_N_B6") (pintype "bidirectional"))
    )
    (net (code "53") (name "unconnected-(IC1-DATA0_P-PadA6)") (class "Default")
      (node (ref "IC1") (pin "A6") (pinfunction "DATA0_P_A6") (pintype "bidirectional"))
    )
    (net (code "54") (name "unconnected-(IC1-DATA1_N-PadA7)") (class "Default")
      (node (ref "IC1") (pin "A7") (pinfunction "DATA1_N_A7") (pintype "bidirectional"))
    )
    (net (code "55") (name "unconnected-(IC1-DATA1_P-PadB7)") (class "Default")
      (node (ref "IC1") (pin "B7") (pinfunction "DATA1_P_B7") (pintype "bidirectional"))
    )
    (net (code "56") (name "unconnected-(IC1-DATA2_N-PadB9)") (class "Default")
      (node (ref "IC1") (pin "B9") (pinfunction "DATA2_N_B9") (pintype "bidirectional"))
    )
    (net (code "57") (name "unconnected-(IC1-DATA2_P-PadA9)") (class "Default")
      (node (ref "IC1") (pin "A9") (pinfunction "DATA2_P_A9") (pintype "bidirectional"))
    )
    (net (code "58") (name "unconnected-(IC1-DATA3_N-PadA10)") (class "Default")
      (node (ref "IC1") (pin "A10") (pinfunction "DATA3_N_A10") (pintype "bidirectional"))
    )
    (net (code "59") (name "unconnected-(IC1-DATA3_P-PadB10)") (class "Default")
      (node (ref "IC1") (pin "B10") (pinfunction "DATA3_P_B10") (pintype "bidirectional"))
    )
    (net (code "60") (name "unconnected-(IC1-GPIO0-PadJ9)") (class "Default")
      (node (ref "IC1") (pin "J9") (pinfunction "GPIO0_J9") (pintype "bidirectional"))
    )
    (net (code "61") (name "unconnected-(IC1-GPIO1-PadJ8)") (class "Default")
      (node (ref "IC1") (pin "J8") (pinfunction "GPIO1_J8") (pintype "bidirectional"))
    )
    (net (code "62") (name "unconnected-(IC1-SYS_CHECK-PadJ10)") (class "Default")
      (node (ref "IC1") (pin "J10") (pinfunction "SYS_CHECK_J10") (pintype "bidirectional"))
    )
    (net (code "63") (name "unconnected-(IC1-TEMP_FLAG-PadH10)") (class "Default")
      (node (ref "IC1") (pin "H10") (pinfunction "TEMP_FLAG_H10") (pintype "bidirectional"))
    )
    (net (code "64") (name "unconnected-(IC1-VPP-PadC11)") (class "Default")
      (node (ref "IC1") (pin "C11") (pinfunction "VPP_C11") (pintype "bidirectional"))
    )
    (net (code "65") (name "unconnected-(IC3-NC-Pad4)") (class "Default")
      (node (ref "IC3") (pin "4") (pinfunction "NC_4") (pintype "passive"))
    )
  )
)
